# PIC_SENSOR-BOARD.net
KiCad netlist of a schematic drawn in EAGLE
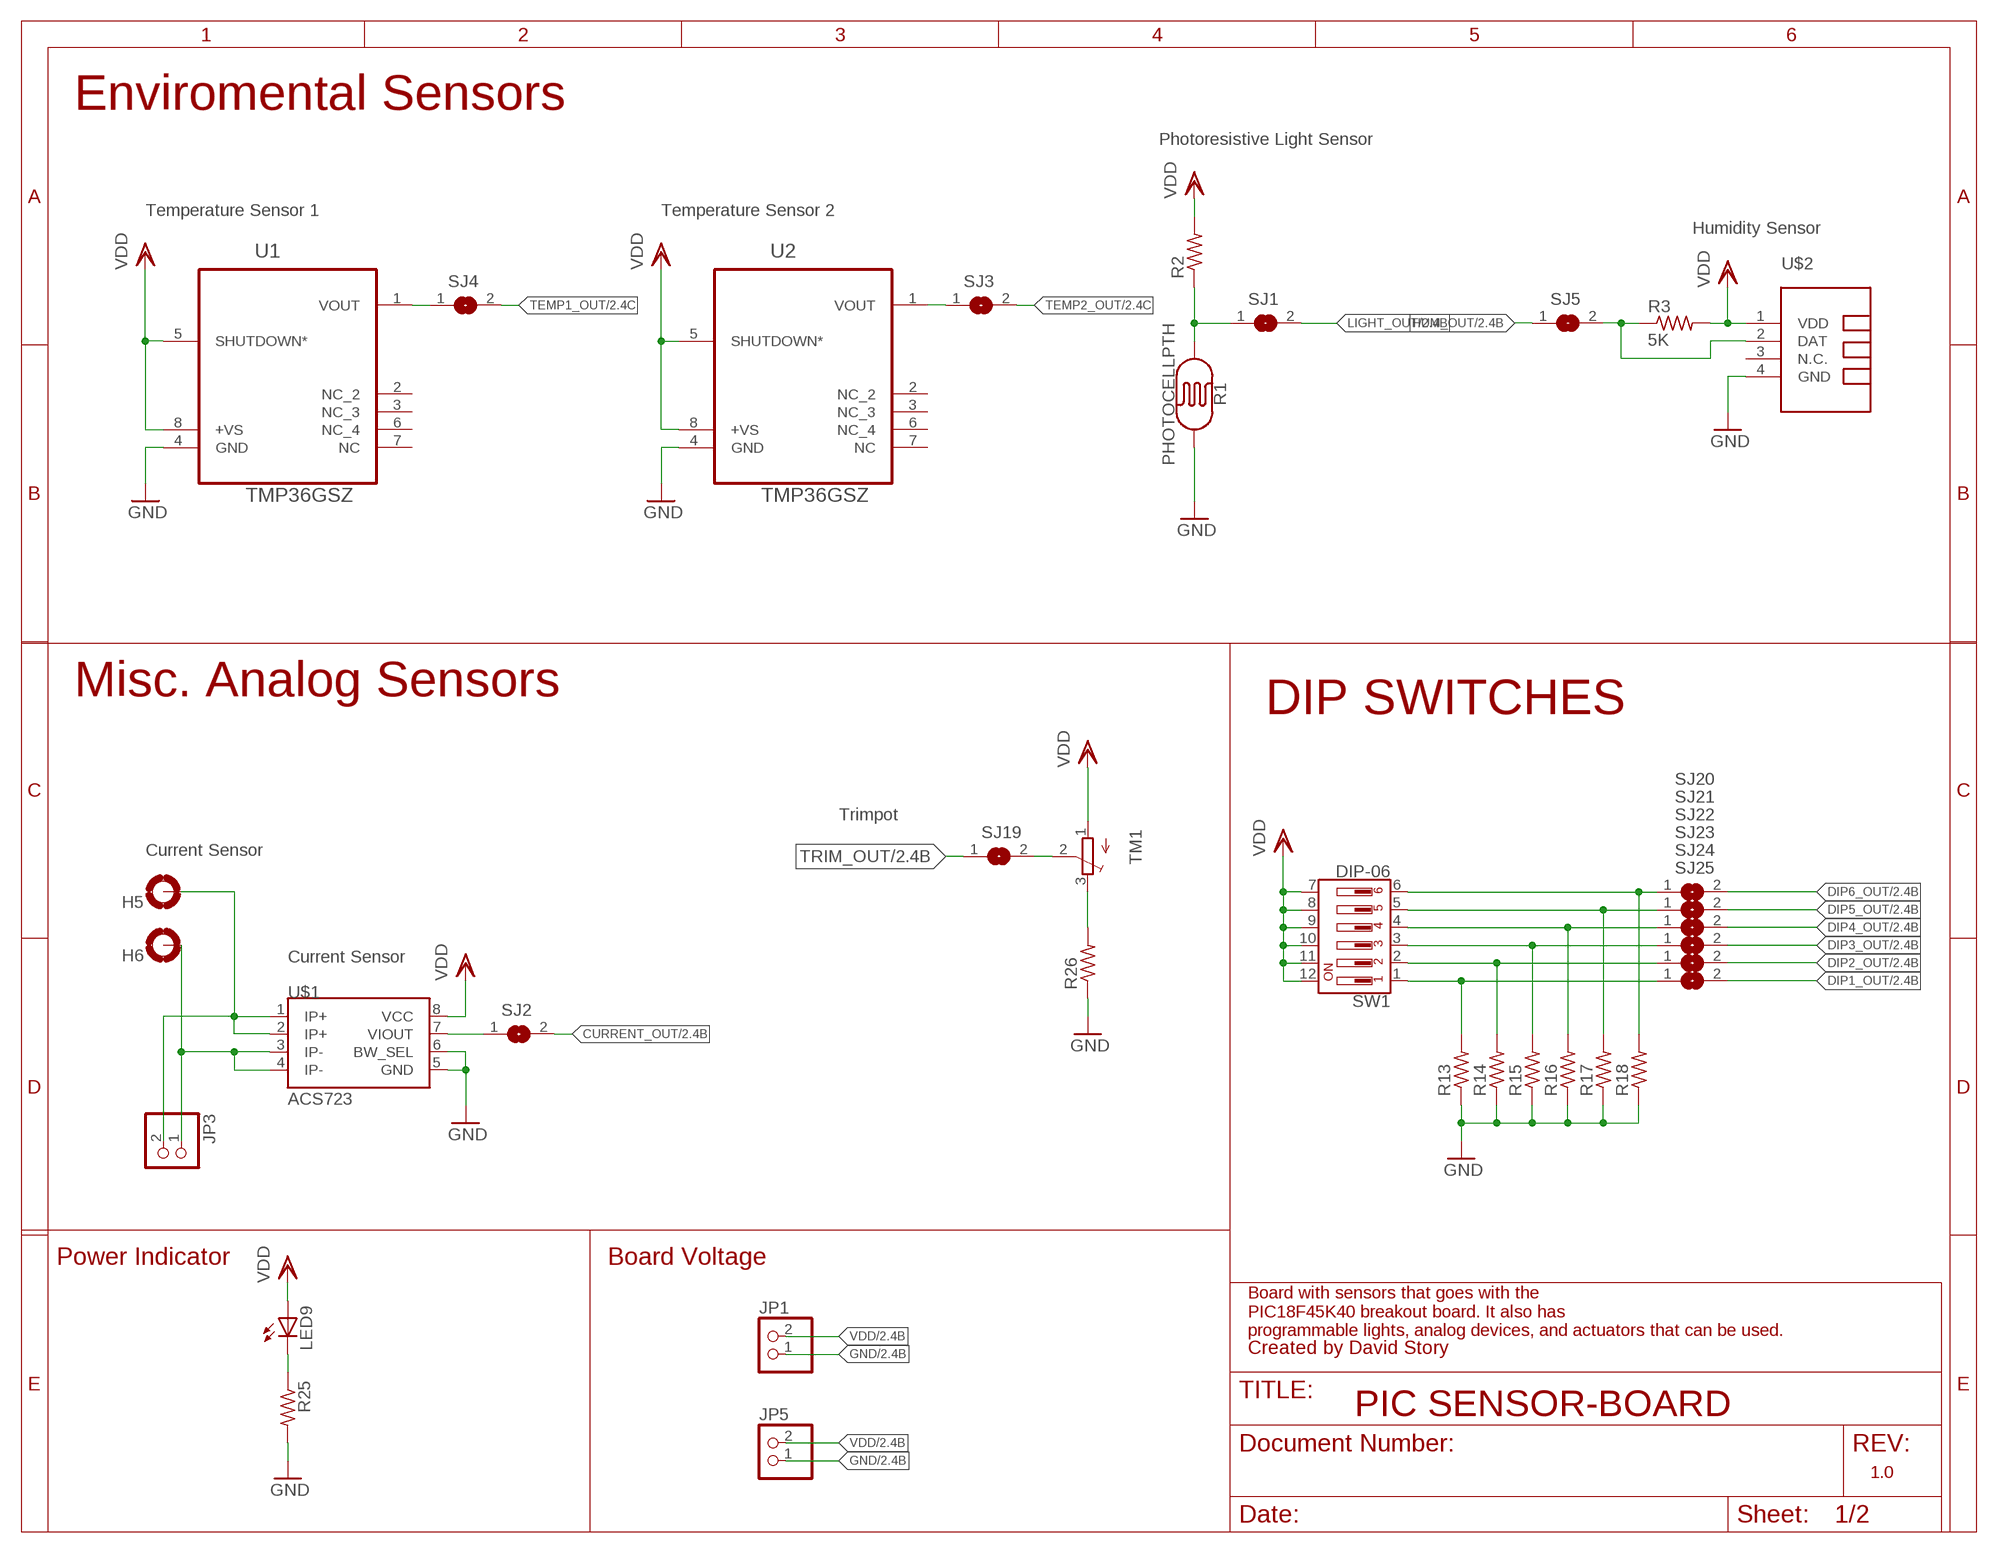
[diagram p0: schematic, sheet 1]
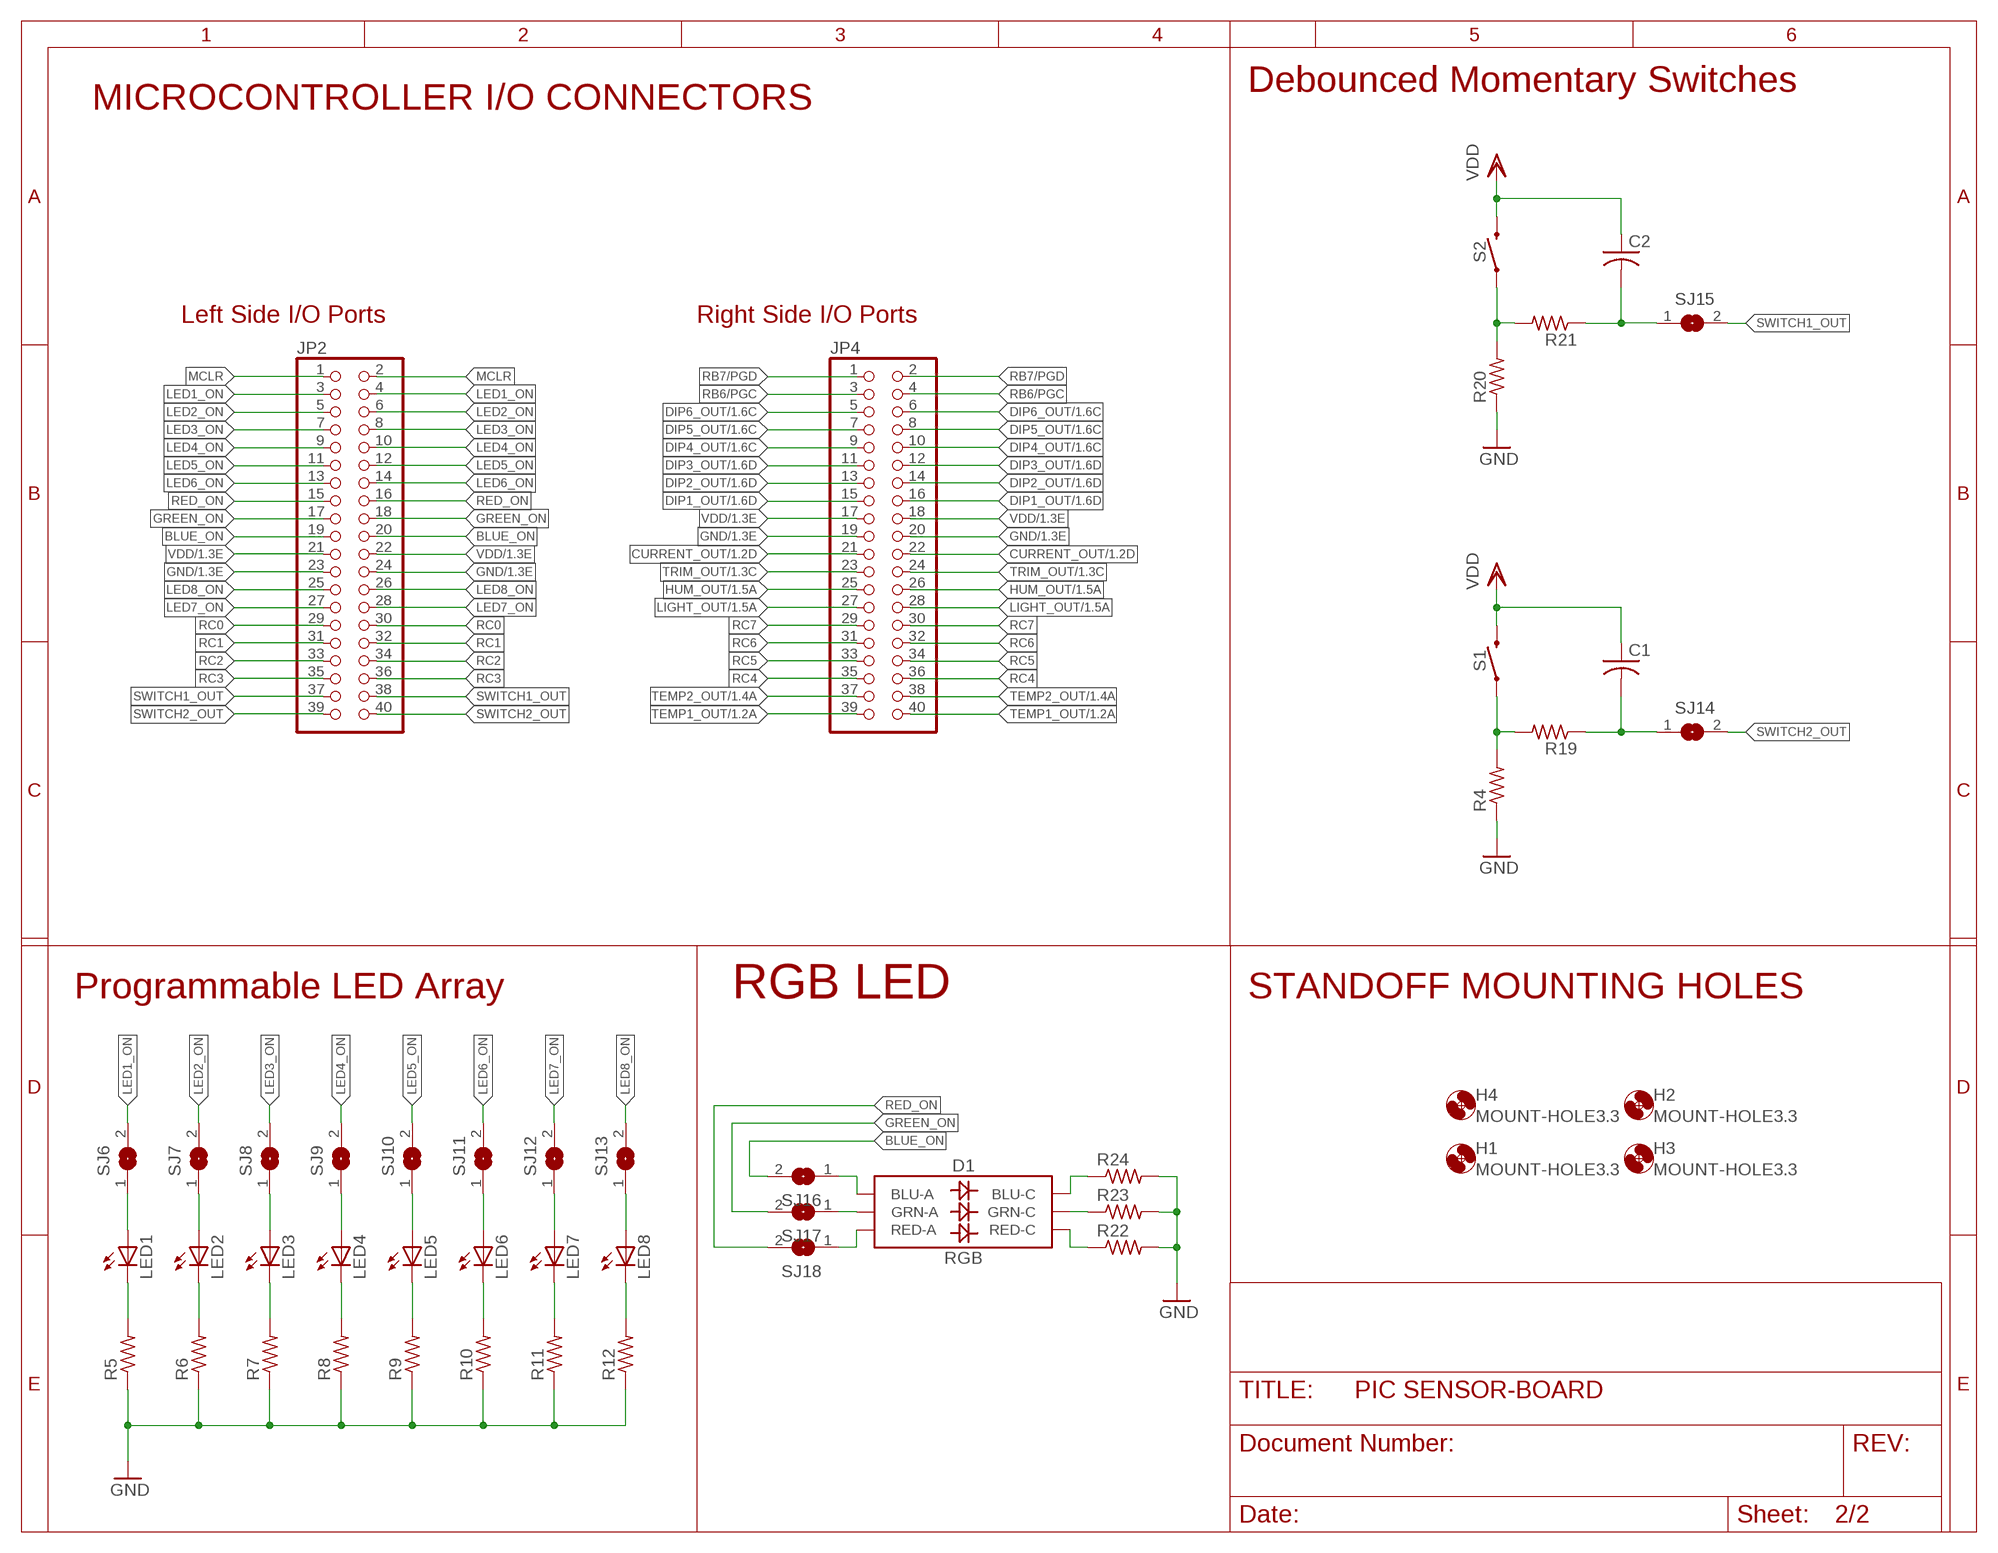
[diagram p1: schematic, sheet 2]

(export (version "E")
  (design (tool "Eeschema 10.0.6"))
  (components
    (comp (ref "H5")
      (value "MOUNT-PAD-ROUND3.3")
      (footprint "eagle-import:3,3-PAD")
      (libsource (lib "eagle-import") (part "MOUNT-PAD-ROUND3.3"))
    )
    (comp (ref "H6")
      (value "MOUNT-PAD-ROUND3.3")
      (footprint "eagle-import:3,3-PAD")
      (libsource (lib "eagle-import") (part "MOUNT-PAD-ROUND3.3"))
    )
    (comp (ref "JP1")
      (value "PINHD-1X2")
      (footprint "eagle-import:1X02")
      (libsource (lib "eagle-import") (part "PINHD-1X2"))
    )
    (comp (ref "JP3")
      (value "PINHD-1X2")
      (footprint "eagle-import:1X02")
      (libsource (lib "eagle-import") (part "PINHD-1X2"))
    )
    (comp (ref "JP5")
      (value "PINHD-1X2")
      (footprint "eagle-import:1X02")
      (libsource (lib "eagle-import") (part "PINHD-1X2"))
    )
    (comp (ref "LED9")
      (value "LEDCHIPLED_0603")
      (footprint "eagle-import:CHIPLED_0603")
      (libsource (lib "eagle-import") (part "LEDCHIPLED_0603"))
    )
    (comp (ref "R1")
      (value "PHOTOCELLPTH")
      (footprint "eagle-import:PHOTOCELL")
      (libsource (lib "eagle-import") (part "PHOTOCELLPTH"))
    )
    (comp (ref "R2")
      (value "R-US_M0805")
      (footprint "eagle-import:M0805")
      (libsource (lib "eagle-import") (part "R-US_M0805"))
    )
    (comp (ref "R3")
      (value "5K")
      (footprint "eagle-import:M0805")
      (libsource (lib "eagle-import") (part "R-US_M0805"))
    )
    (comp (ref "R13")
      (value "R-US_R0805")
      (footprint "eagle-import:R0805")
      (libsource (lib "eagle-import") (part "R-US_R0805"))
    )
    (comp (ref "R14")
      (value "R-US_R0805")
      (footprint "eagle-import:R0805")
      (libsource (lib "eagle-import") (part "R-US_R0805"))
    )
    (comp (ref "R15")
      (value "R-US_R0805")
      (footprint "eagle-import:R0805")
      (libsource (lib "eagle-import") (part "R-US_R0805"))
    )
    (comp (ref "R16")
      (value "R-US_R0805")
      (footprint "eagle-import:R0805")
      (libsource (lib "eagle-import") (part "R-US_R0805"))
    )
    (comp (ref "R17")
      (value "R-US_R0805")
      (footprint "eagle-import:R0805")
      (libsource (lib "eagle-import") (part "R-US_R0805"))
    )
    (comp (ref "R18")
      (value "R-US_R0805")
      (footprint "eagle-import:R0805")
      (libsource (lib "eagle-import") (part "R-US_R0805"))
    )
    (comp (ref "R25")
      (value "R-US_M0805")
      (footprint "eagle-import:M0805")
      (libsource (lib "eagle-import") (part "R-US_M0805"))
    )
    (comp (ref "R26")
      (value "R-US_M0805")
      (footprint "eagle-import:M0805")
      (libsource (lib "eagle-import") (part "R-US_M0805"))
    )
    (comp (ref "SJ1") (value "SJ") (footprint "eagle-import:SJ") (libsource (lib "eagle-import") (part "SJ")))
    (comp (ref "SJ2") (value "SJ") (footprint "eagle-import:SJ") (libsource (lib "eagle-import") (part "SJ")))
    (comp (ref "SJ3") (value "SJ") (footprint "eagle-import:SJ") (libsource (lib "eagle-import") (part "SJ")))
    (comp (ref "SJ4") (value "SJ") (footprint "eagle-import:SJ") (libsource (lib "eagle-import") (part "SJ")))
    (comp (ref "SJ5") (value "SJ") (footprint "eagle-import:SJ") (libsource (lib "eagle-import") (part "SJ")))
    (comp (ref "SJ19")
      (value "SJ")
      (footprint "eagle-import:SJ")
      (libsource (lib "eagle-import") (part "SJ"))
    )
    (comp (ref "SJ20")
      (value "SJ")
      (footprint "eagle-import:SJ")
      (libsource (lib "eagle-import") (part "SJ"))
    )
    (comp (ref "SJ21")
      (value "SJ")
      (footprint "eagle-import:SJ")
      (libsource (lib "eagle-import") (part "SJ"))
    )
    (comp (ref "SJ22")
      (value "SJ")
      (footprint "eagle-import:SJ")
      (libsource (lib "eagle-import") (part "SJ"))
    )
    (comp (ref "SJ23")
      (value "SJ")
      (footprint "eagle-import:SJ")
      (libsource (lib "eagle-import") (part "SJ"))
    )
    (comp (ref "SJ24")
      (value "SJ")
      (footprint "eagle-import:SJ")
      (libsource (lib "eagle-import") (part "SJ"))
    )
    (comp (ref "SJ25")
      (value "SJ")
      (footprint "eagle-import:SJ")
      (libsource (lib "eagle-import") (part "SJ"))
    )
    (comp (ref "SW1")
      (value "DIP-06")
      (footprint "eagle-import:DIPSWITCH-06-SMD")
      (libsource (lib "eagle-import") (part "DIP-06"))
    )
    (comp (ref "TM1")
      (value "TRIMPOT3386")
      (footprint "eagle-import:TRIM-3386")
      (libsource (lib "eagle-import") (part "TRIMPOT3386"))
    )
    (comp (ref "U$1")
      (value "ACS723")
      (footprint "eagle-import:SO08")
      (fields (field (name "PART_#") "ACS723ACS723LLCTR-05AB-T2"))
      (libsource (lib "eagle-import") (part "ACS723"))
    )
    (comp (ref "U$2")
      (value "TEMP-HUM-SENSOR-DHT11")
      (footprint "eagle-import:TEMP-HUM-SENSOR-DHT11")
      (libsource (lib "eagle-import") (part "TEMP-HUM-SENSOR-DHT11"))
    )
    (comp (ref "U1")
      (value "TMP36GSZ")
      (footprint "eagle-import:SOIC127P600X175-8N")
      (libsource (lib "eagle-import") (part "TMP36GSZ"))
    )
    (comp (ref "U2")
      (value "TMP36GSZ")
      (footprint "eagle-import:SOIC127P600X175-8N")
      (libsource (lib "eagle-import") (part "TMP36GSZ"))
    )
    (comp (ref "C1")
      (value "C-USC0805")
      (footprint "eagle-import:C0805")
      (libsource (lib "eagle-import") (part "C-USC0805"))
    )
    (comp (ref "C2")
      (value "C-USC0805")
      (footprint "eagle-import:C0805")
      (libsource (lib "eagle-import") (part "C-USC0805"))
    )
    (comp (ref "D1")
      (value "RGB")
      (footprint "eagle-import:PLCC-6-LED")
      (libsource (lib "eagle-import") (part "LED-RGBPLCC-6"))
    )
    (comp (ref "H1")
      (value "MOUNT-HOLE3.3")
      (footprint "eagle-import:3,3")
      (libsource (lib "eagle-import") (part "MOUNT-HOLE3.3"))
    )
    (comp (ref "H2")
      (value "MOUNT-HOLE3.3")
      (footprint "eagle-import:3,3")
      (libsource (lib "eagle-import") (part "MOUNT-HOLE3.3"))
    )
    (comp (ref "H3")
      (value "MOUNT-HOLE3.3")
      (footprint "eagle-import:3,3")
      (libsource (lib "eagle-import") (part "MOUNT-HOLE3.3"))
    )
    (comp (ref "H4")
      (value "MOUNT-HOLE3.3")
      (footprint "eagle-import:3,3")
      (libsource (lib "eagle-import") (part "MOUNT-HOLE3.3"))
    )
    (comp (ref "JP2")
      (value "PINHD-2X20")
      (footprint "eagle-import:2X20")
      (libsource (lib "eagle-import") (part "PINHD-2X20"))
    )
    (comp (ref "JP4")
      (value "PINHD-2X20")
      (footprint "eagle-import:2X20")
      (libsource (lib "eagle-import") (part "PINHD-2X20"))
    )
    (comp (ref "LED1")
      (value "LEDSML0603")
      (footprint "eagle-import:SML0603")
      (libsource (lib "eagle-import") (part "LEDSML0603"))
    )
    (comp (ref "LED2")
      (value "LEDSML0603")
      (footprint "eagle-import:SML0603")
      (libsource (lib "eagle-import") (part "LEDSML0603"))
    )
    (comp (ref "LED3")
      (value "LEDSML0603")
      (footprint "eagle-import:SML0603")
      (libsource (lib "eagle-import") (part "LEDSML0603"))
    )
    (comp (ref "LED4")
      (value "LEDSML0603")
      (footprint "eagle-import:SML0603")
      (libsource (lib "eagle-import") (part "LEDSML0603"))
    )
    (comp (ref "LED5")
      (value "LEDSML0603")
      (footprint "eagle-import:SML0603")
      (libsource (lib "eagle-import") (part "LEDSML0603"))
    )
    (comp (ref "LED6")
      (value "LEDSML0603")
      (footprint "eagle-import:SML0603")
      (libsource (lib "eagle-import") (part "LEDSML0603"))
    )
    (comp (ref "LED7")
      (value "LEDSML0603")
      (footprint "eagle-import:SML0603")
      (libsource (lib "eagle-import") (part "LEDSML0603"))
    )
    (comp (ref "LED8")
      (value "LEDSML0603")
      (footprint "eagle-import:SML0603")
      (libsource (lib "eagle-import") (part "LEDSML0603"))
    )
    (comp (ref "R4")
      (value "R-US_M0805")
      (footprint "eagle-import:M0805")
      (libsource (lib "eagle-import") (part "R-US_M0805"))
    )
    (comp (ref "R5")
      (value "R-US_M0805")
      (footprint "eagle-import:M0805")
      (libsource (lib "eagle-import") (part "R-US_M0805"))
    )
    (comp (ref "R6")
      (value "R-US_M0805")
      (footprint "eagle-import:M0805")
      (libsource (lib "eagle-import") (part "R-US_M0805"))
    )
    (comp (ref "R7")
      (value "R-US_M0805")
      (footprint "eagle-import:M0805")
      (libsource (lib "eagle-import") (part "R-US_M0805"))
    )
    (comp (ref "R8")
      (value "R-US_M0805")
      (footprint "eagle-import:M0805")
      (libsource (lib "eagle-import") (part "R-US_M0805"))
    )
    (comp (ref "R9")
      (value "R-US_M0805")
      (footprint "eagle-import:M0805")
      (libsource (lib "eagle-import") (part "R-US_M0805"))
    )
    (comp (ref "R10")
      (value "R-US_M0805")
      (footprint "eagle-import:M0805")
      (libsource (lib "eagle-import") (part "R-US_M0805"))
    )
    (comp (ref "R11")
      (value "R-US_M0805")
      (footprint "eagle-import:M0805")
      (libsource (lib "eagle-import") (part "R-US_M0805"))
    )
    (comp (ref "R12")
      (value "R-US_M0805")
      (footprint "eagle-import:M0805")
      (libsource (lib "eagle-import") (part "R-US_M0805"))
    )
    (comp (ref "R19")
      (value "R-US_M0805")
      (footprint "eagle-import:M0805")
      (libsource (lib "eagle-import") (part "R-US_M0805"))
    )
    (comp (ref "R20")
      (value "R-US_M0805")
      (footprint "eagle-import:M0805")
      (libsource (lib "eagle-import") (part "R-US_M0805"))
    )
    (comp (ref "R21")
      (value "R-US_M0805")
      (footprint "eagle-import:M0805")
      (libsource (lib "eagle-import") (part "R-US_M0805"))
    )
    (comp (ref "R22")
      (value "R-US_R0805")
      (footprint "eagle-import:R0805")
      (libsource (lib "eagle-import") (part "R-US_R0805"))
    )
    (comp (ref "R23")
      (value "R-US_R0805")
      (footprint "eagle-import:R0805")
      (libsource (lib "eagle-import") (part "R-US_R0805"))
    )
    (comp (ref "R24")
      (value "R-US_R0805")
      (footprint "eagle-import:R0805")
      (libsource (lib "eagle-import") (part "R-US_R0805"))
    )
    (comp (ref "S1")
      (value "MOMENTARY-SWITCH-SPST-PTH-6.0MM")
      (footprint "eagle-import:TACTILE_SWITCH_PTH_6.0MM")
      (libsource (lib "eagle-import") (part "MOMENTARY-SWITCH-SPST-PTH-6.0MM"))
    )
    (comp (ref "S2")
      (value "MOMENTARY-SWITCH-SPST-PTH-6.0MM")
      (footprint "eagle-import:TACTILE_SWITCH_PTH_6.0MM")
      (libsource (lib "eagle-import") (part "MOMENTARY-SWITCH-SPST-PTH-6.0MM"))
    )
    (comp (ref "SJ6") (value "SJ") (footprint "eagle-import:SJ") (libsource (lib "eagle-import") (part "SJ")))
    (comp (ref "SJ7") (value "SJ") (footprint "eagle-import:SJ") (libsource (lib "eagle-import") (part "SJ")))
    (comp (ref "SJ8") (value "SJ") (footprint "eagle-import:SJ") (libsource (lib "eagle-import") (part "SJ")))
    (comp (ref "SJ9") (value "SJ") (footprint "eagle-import:SJ") (libsource (lib "eagle-import") (part "SJ")))
    (comp (ref "SJ10")
      (value "SJ")
      (footprint "eagle-import:SJ")
      (libsource (lib "eagle-import") (part "SJ"))
    )
    (comp (ref "SJ11")
      (value "SJ")
      (footprint "eagle-import:SJ")
      (libsource (lib "eagle-import") (part "SJ"))
    )
    (comp (ref "SJ12")
      (value "SJ")
      (footprint "eagle-import:SJ")
      (libsource (lib "eagle-import") (part "SJ"))
    )
    (comp (ref "SJ13")
      (value "SJ")
      (footprint "eagle-import:SJ")
      (libsource (lib "eagle-import") (part "SJ"))
    )
    (comp (ref "SJ14")
      (value "SJ")
      (footprint "eagle-import:SJ")
      (libsource (lib "eagle-import") (part "SJ"))
    )
    (comp (ref "SJ15")
      (value "SJ")
      (footprint "eagle-import:SJ")
      (libsource (lib "eagle-import") (part "SJ"))
    )
    (comp (ref "SJ16")
      (value "SJ")
      (footprint "eagle-import:SJ")
      (libsource (lib "eagle-import") (part "SJ"))
    )
    (comp (ref "SJ17")
      (value "SJ")
      (footprint "eagle-import:SJ")
      (libsource (lib "eagle-import") (part "SJ"))
    )
    (comp (ref "SJ18")
      (value "SJ")
      (footprint "eagle-import:SJ")
      (libsource (lib "eagle-import") (part "SJ"))
    )
  )
  (nets
    (net (code "1") (name "BLUE_ON") (class "Default")
      (node (ref "JP2") (pin "19") (pinfunction "19_19") (pintype "passive"))
      (node (ref "JP2") (pin "20") (pinfunction "20_20") (pintype "passive"))
      (node (ref "SJ16") (pin "2") (pinfunction "2_2") (pintype "passive"))
    )
    (net (code "2") (name "CURRENT_OUT") (class "Default")
      (node (ref "JP4") (pin "21") (pinfunction "21_21") (pintype "passive"))
      (node (ref "JP4") (pin "22") (pinfunction "22_22") (pintype "passive"))
      (node (ref "SJ2") (pin "2") (pinfunction "2_2") (pintype "passive"))
    )
    (net (code "3") (name "DIP1_OUT") (class "Default")
      (node (ref "JP4") (pin "15") (pinfunction "15_15") (pintype "passive"))
      (node (ref "JP4") (pin "16") (pinfunction "16_16") (pintype "passive"))
      (node (ref "SJ25") (pin "2") (pinfunction "2_2") (pintype "passive"))
    )
    (net (code "4") (name "DIP2_OUT") (class "Default")
      (node (ref "JP4") (pin "13") (pinfunction "13_13") (pintype "passive"))
      (node (ref "JP4") (pin "14") (pinfunction "14_14") (pintype "passive"))
      (node (ref "SJ24") (pin "2") (pinfunction "2_2") (pintype "passive"))
    )
    (net (code "5") (name "DIP3_OUT") (class "Default")
      (node (ref "JP4") (pin "11") (pinfunction "11_11") (pintype "passive"))
      (node (ref "JP4") (pin "12") (pinfunction "12_12") (pintype "passive"))
      (node (ref "SJ23") (pin "2") (pinfunction "2_2") (pintype "passive"))
    )
    (net (code "6") (name "DIP4_OUT") (class "Default")
      (node (ref "JP4") (pin "10") (pinfunction "10_10") (pintype "passive"))
      (node (ref "JP4") (pin "9") (pinfunction "9_9") (pintype "passive"))
      (node (ref "SJ22") (pin "2") (pinfunction "2_2") (pintype "passive"))
    )
    (net (code "7") (name "DIP5_OUT") (class "Default")
      (node (ref "JP4") (pin "7") (pinfunction "7_7") (pintype "passive"))
      (node (ref "JP4") (pin "8") (pinfunction "8_8") (pintype "passive"))
      (node (ref "SJ21") (pin "2") (pinfunction "2_2") (pintype "passive"))
    )
    (net (code "8") (name "DIP6_OUT") (class "Default")
      (node (ref "JP4") (pin "5") (pinfunction "5_5") (pintype "passive"))
      (node (ref "JP4") (pin "6") (pinfunction "6_6") (pintype "passive"))
      (node (ref "SJ20") (pin "2") (pinfunction "2_2") (pintype "passive"))
    )
    (net (code "9") (name "GND") (class "Default")
      (node (ref "JP1") (pin "1") (pinfunction "1_1") (pintype "passive"))
      (node (ref "JP2") (pin "23") (pinfunction "23_23") (pintype "passive"))
      (node (ref "JP2") (pin "24") (pinfunction "24_24") (pintype "passive"))
      (node (ref "JP4") (pin "19") (pinfunction "19_19") (pintype "passive"))
      (node (ref "JP4") (pin "20") (pinfunction "20_20") (pintype "passive"))
      (node (ref "JP5") (pin "1") (pinfunction "1_1") (pintype "passive"))
      (node (ref "R1") (pin "2") (pinfunction "P$2_2") (pintype "bidirectional"))
      (node (ref "R10") (pin "1") (pinfunction "1_1") (pintype "passive"))
      (node (ref "R11") (pin "1") (pinfunction "1_1") (pintype "passive"))
      (node (ref "R12") (pin "1") (pinfunction "1_1") (pintype "passive"))
      (node (ref "R13") (pin "1") (pinfunction "1_1") (pintype "passive"))
      (node (ref "R14") (pin "1") (pinfunction "1_1") (pintype "passive"))
      (node (ref "R15") (pin "1") (pinfunction "1_1") (pintype "passive"))
      (node (ref "R16") (pin "1") (pinfunction "1_1") (pintype "passive"))
      (node (ref "R17") (pin "1") (pinfunction "1_1") (pintype "passive"))
      (node (ref "R18") (pin "1") (pinfunction "1_1") (pintype "passive"))
      (node (ref "R20") (pin "1") (pinfunction "1_1") (pintype "passive"))
      (node (ref "R22") (pin "2") (pinfunction "2_2") (pintype "passive"))
      (node (ref "R23") (pin "2") (pinfunction "2_2") (pintype "passive"))
      (node (ref "R24") (pin "2") (pinfunction "2_2") (pintype "passive"))
      (node (ref "R25") (pin "2") (pinfunction "2_2") (pintype "passive"))
      (node (ref "R26") (pin "1") (pinfunction "1_1") (pintype "passive"))
      (node (ref "R4") (pin "1") (pinfunction "1_1") (pintype "passive"))
      (node (ref "R5") (pin "1") (pinfunction "1_1") (pintype "passive"))
      (node (ref "R6") (pin "1") (pinfunction "1_1") (pintype "passive"))
      (node (ref "R7") (pin "1") (pinfunction "1_1") (pintype "passive"))
      (node (ref "R8") (pin "1") (pinfunction "1_1") (pintype "passive"))
      (node (ref "R9") (pin "1") (pinfunction "1_1") (pintype "passive"))
      (node (ref "U$1") (pin "5") (pinfunction "GND_5") (pintype "bidirectional"))
      (node (ref "U$1") (pin "6") (pinfunction "BW_SEL_6") (pintype "bidirectional"))
      (node (ref "U$2") (pin "4") (pinfunction "GND_4") (pintype "power_in"))
      (node (ref "U1") (pin "4") (pinfunction "GND_4") (pintype "passive"))
      (node (ref "U2") (pin "4") (pinfunction "GND_4") (pintype "passive"))
    )
    (net (code "10") (name "GREEN_ON") (class "Default")
      (node (ref "JP2") (pin "17") (pinfunction "17_17") (pintype "passive"))
      (node (ref "JP2") (pin "18") (pinfunction "18_18") (pintype "passive"))
      (node (ref "SJ17") (pin "2") (pinfunction "2_2") (pintype "passive"))
    )
    (net (code "11") (name "HUM_OUT") (class "Default")
      (node (ref "JP4") (pin "25") (pinfunction "25_25") (pintype "passive"))
      (node (ref "JP4") (pin "26") (pinfunction "26_26") (pintype "passive"))
      (node (ref "SJ5") (pin "1") (pinfunction "1_1") (pintype "passive"))
    )
    (net (code "12") (name "LED1_ON") (class "Default")
      (node (ref "JP2") (pin "3") (pinfunction "3_3") (pintype "passive"))
      (node (ref "JP2") (pin "4") (pinfunction "4_4") (pintype "passive"))
      (node (ref "SJ6") (pin "2") (pinfunction "2_2") (pintype "passive"))
    )
    (net (code "13") (name "LED2_ON") (class "Default")
      (node (ref "JP2") (pin "5") (pinfunction "5_5") (pintype "passive"))
      (node (ref "JP2") (pin "6") (pinfunction "6_6") (pintype "passive"))
      (node (ref "SJ7") (pin "2") (pinfunction "2_2") (pintype "passive"))
    )
    (net (code "14") (name "LED3_ON") (class "Default")
      (node (ref "JP2") (pin "7") (pinfunction "7_7") (pintype "passive"))
      (node (ref "JP2") (pin "8") (pinfunction "8_8") (pintype "passive"))
      (node (ref "SJ8") (pin "2") (pinfunction "2_2") (pintype "passive"))
    )
    (net (code "15") (name "LED4_ON") (class "Default")
      (node (ref "JP2") (pin "10") (pinfunction "10_10") (pintype "passive"))
      (node (ref "JP2") (pin "9") (pinfunction "9_9") (pintype "passive"))
      (node (ref "SJ9") (pin "2") (pinfunction "2_2") (pintype "passive"))
    )
    (net (code "16") (name "LED5_ON") (class "Default")
      (node (ref "JP2") (pin "11") (pinfunction "11_11") (pintype "passive"))
      (node (ref "JP2") (pin "12") (pinfunction "12_12") (pintype "passive"))
      (node (ref "SJ10") (pin "2") (pinfunction "2_2") (pintype "passive"))
    )
    (net (code "17") (name "LED6_ON") (class "Default")
      (node (ref "JP2") (pin "13") (pinfunction "13_13") (pintype "passive"))
      (node (ref "JP2") (pin "14") (pinfunction "14_14") (pintype "passive"))
      (node (ref "SJ11") (pin "2") (pinfunction "2_2") (pintype "passive"))
    )
    (net (code "18") (name "LED7_ON") (class "Default")
      (node (ref "JP2") (pin "27") (pinfunction "27_27") (pintype "passive"))
      (node (ref "JP2") (pin "28") (pinfunction "28_28") (pintype "passive"))
      (node (ref "SJ12") (pin "2") (pinfunction "2_2") (pintype "passive"))
    )
    (net (code "19") (name "LED8_ON") (class "Default")
      (node (ref "JP2") (pin "25") (pinfunction "25_25") (pintype "passive"))
      (node (ref "JP2") (pin "26") (pinfunction "26_26") (pintype "passive"))
      (node (ref "SJ13") (pin "2") (pinfunction "2_2") (pintype "passive"))
    )
    (net (code "20") (name "LIGHT_OUT") (class "Default")
      (node (ref "JP4") (pin "27") (pinfunction "27_27") (pintype "passive"))
      (node (ref "JP4") (pin "28") (pinfunction "28_28") (pintype "passive"))
      (node (ref "SJ1") (pin "2") (pinfunction "2_2") (pintype "passive"))
    )
    (net (code "21") (name "MCLR") (class "Default")
      (node (ref "JP2") (pin "1") (pinfunction "1_1") (pintype "passive"))
      (node (ref "JP2") (pin "2") (pinfunction "2_2") (pintype "passive"))
    )
    (net (code "22") (name "Net-(C1-Pad2)") (class "Default")
      (node (ref "C1") (pin "2") (pinfunction "2_2") (pintype "passive"))
      (node (ref "R19") (pin "1") (pinfunction "1_1") (pintype "passive"))
      (node (ref "SJ14") (pin "1") (pinfunction "1_1") (pintype "passive"))
    )
    (net (code "23") (name "Net-(C2-Pad2)") (class "Default")
      (node (ref "C2") (pin "2") (pinfunction "2_2") (pintype "passive"))
      (node (ref "R21") (pin "1") (pinfunction "1_1") (pintype "passive"))
      (node (ref "SJ15") (pin "1") (pinfunction "1_1") (pintype "passive"))
    )
    (net (code "24") (name "Net-(D1-BLU-A)") (class "Default")
      (node (ref "D1") (pin "AB") (pinfunction "BLU-A_AB") (pintype "bidirectional"))
      (node (ref "SJ16") (pin "1") (pinfunction "1_1") (pintype "passive"))
    )
    (net (code "25") (name "Net-(D1-BLU-C)") (class "Default")
      (node (ref "D1") (pin "CB") (pinfunction "BLU-C_CB") (pintype "bidirectional"))
      (node (ref "R24") (pin "1") (pinfunction "1_1") (pintype "passive"))
    )
    (net (code "26") (name "Net-(D1-GRN-A)") (class "Default")
      (node (ref "D1") (pin "AG") (pinfunction "GRN-A_AG") (pintype "bidirectional"))
      (node (ref "SJ17") (pin "1") (pinfunction "1_1") (pintype "passive"))
    )
    (net (code "27") (name "Net-(D1-GRN-C)") (class "Default")
      (node (ref "D1") (pin "CG") (pinfunction "GRN-C_CG") (pintype "bidirectional"))
      (node (ref "R23") (pin "1") (pinfunction "1_1") (pintype "passive"))
    )
    (net (code "28") (name "Net-(D1-RED-A)") (class "Default")
      (node (ref "D1") (pin "AR") (pinfunction "RED-A_AR") (pintype "bidirectional"))
      (node (ref "SJ18") (pin "1") (pinfunction "1_1") (pintype "passive"))
    )
    (net (code "29") (name "Net-(D1-RED-C)") (class "Default")
      (node (ref "D1") (pin "CR") (pinfunction "RED-C_CR") (pintype "bidirectional"))
      (node (ref "R22") (pin "1") (pinfunction "1_1") (pintype "passive"))
    )
    (net (code "30") (name "Net-(H5-MOUNT)") (class "Default")
      (node (ref "H5") (pin "B3,3") (pinfunction "MOUNT_B3,3") (pintype "passive"))
      (node (ref "JP3") (pin "2") (pinfunction "2_2") (pintype "passive"))
      (node (ref "U$1") (pin "1") (pinfunction "IP+_1") (pintype "input"))
      (node (ref "U$1") (pin "2") (pinfunction "IP+_2") (pintype "input"))
    )
    (net (code "31") (name "Net-(H6-MOUNT)") (class "Default")
      (node (ref "H6") (pin "B3,3") (pinfunction "MOUNT_B3,3") (pintype "passive"))
      (node (ref "JP3") (pin "1") (pinfunction "1_1") (pintype "passive"))
      (node (ref "U$1") (pin "3") (pinfunction "IP-_3") (pintype "bidirectional"))
      (node (ref "U$1") (pin "4") (pinfunction "IP-_4") (pintype "bidirectional"))
    )
    (net (code "32") (name "Net-(LED1-PadA)") (class "Default")
      (node (ref "LED1") (pin "A") (pinfunction "A_A") (pintype "passive"))
      (node (ref "SJ6") (pin "1") (pinfunction "1_1") (pintype "passive"))
    )
    (net (code "33") (name "Net-(LED1-PadC)") (class "Default")
      (node (ref "LED1") (pin "C") (pinfunction "C_C") (pintype "passive"))
      (node (ref "R5") (pin "2") (pinfunction "2_2") (pintype "passive"))
    )
    (net (code "34") (name "Net-(LED2-PadA)") (class "Default")
      (node (ref "LED2") (pin "A") (pinfunction "A_A") (pintype "passive"))
      (node (ref "SJ7") (pin "1") (pinfunction "1_1") (pintype "passive"))
    )
    (net (code "35") (name "Net-(LED2-PadC)") (class "Default")
      (node (ref "LED2") (pin "C") (pinfunction "C_C") (pintype "passive"))
      (node (ref "R6") (pin "2") (pinfunction "2_2") (pintype "passive"))
    )
    (net (code "36") (name "Net-(LED3-PadA)") (class "Default")
      (node (ref "LED3") (pin "A") (pinfunction "A_A") (pintype "passive"))
      (node (ref "SJ8") (pin "1") (pinfunction "1_1") (pintype "passive"))
    )
    (net (code "37") (name "Net-(LED3-PadC)") (class "Default")
      (node (ref "LED3") (pin "C") (pinfunction "C_C") (pintype "passive"))
      (node (ref "R7") (pin "2") (pinfunction "2_2") (pintype "passive"))
    )
    (net (code "38") (name "Net-(LED4-PadA)") (class "Default")
      (node (ref "LED4") (pin "A") (pinfunction "A_A") (pintype "passive"))
      (node (ref "SJ9") (pin "1") (pinfunction "1_1") (pintype "passive"))
    )
    (net (code "39") (name "Net-(LED4-PadC)") (class "Default")
      (node (ref "LED4") (pin "C") (pinfunction "C_C") (pintype "passive"))
      (node (ref "R8") (pin "2") (pinfunction "2_2") (pintype "passive"))
    )
    (net (code "40") (name "Net-(LED5-PadA)") (class "Default")
      (node (ref "LED5") (pin "A") (pinfunction "A_A") (pintype "passive"))
      (node (ref "SJ10") (pin "1") (pinfunction "1_1") (pintype "passive"))
    )
    (net (code "41") (name "Net-(LED5-PadC)") (class "Default")
      (node (ref "LED5") (pin "C") (pinfunction "C_C") (pintype "passive"))
      (node (ref "R9") (pin "2") (pinfunction "2_2") (pintype "passive"))
    )
    (net (code "42") (name "Net-(LED6-PadA)") (class "Default")
      (node (ref "LED6") (pin "A") (pinfunction "A_A") (pintype "passive"))
      (node (ref "SJ11") (pin "1") (pinfunction "1_1") (pintype "passive"))
    )
    (net (code "43") (name "Net-(LED6-PadC)") (class "Default")
      (node (ref "LED6") (pin "C") (pinfunction "C_C") (pintype "passive"))
      (node (ref "R10") (pin "2") (pinfunction "2_2") (pintype "passive"))
    )
    (net (code "44") (name "Net-(LED7-PadA)") (class "Default")
      (node (ref "LED7") (pin "A") (pinfunction "A_A") (pintype "passive"))
      (node (ref "SJ12") (pin "1") (pinfunction "1_1") (pintype "passive"))
    )
    (net (code "45") (name "Net-(LED7-PadC)") (class "Default")
      (node (ref "LED7") (pin "C") (pinfunction "C_C") (pintype "passive"))
      (node (ref "R11") (pin "2") (pinfunction "2_2") (pintype "passive"))
    )
    (net (code "46") (name "Net-(LED8-PadA)") (class "Default")
      (node (ref "LED8") (pin "A") (pinfunction "A_A") (pintype "passive"))
      (node (ref "SJ13") (pin "1") (pinfunction "1_1") (pintype "passive"))
    )
    (net (code "47") (name "Net-(LED8-PadC)") (class "Default")
      (node (ref "LED8") (pin "C") (pinfunction "C_C") (pintype "passive"))
      (node (ref "R12") (pin "2") (pinfunction "2_2") (pintype "passive"))
    )
    (net (code "48") (name "Net-(LED9-PadC)") (class "Default")
      (node (ref "LED9") (pin "C") (pinfunction "C_C") (pintype "passive"))
      (node (ref "R25") (pin "1") (pinfunction "1_1") (pintype "passive"))
    )
    (net (code "49") (name "Net-(R1-P$1)") (class "Default")
      (node (ref "R1") (pin "1") (pinfunction "P$1_1") (pintype "bidirectional"))
      (node (ref "R2") (pin "1") (pinfunction "1_1") (pintype "passive"))
      (node (ref "SJ1") (pin "1") (pinfunction "1_1") (pintype "passive"))
    )
    (net (code "50") (name "Net-(R13-Pad2)") (class "Default")
      (node (ref "R13") (pin "2") (pinfunction "2_2") (pintype "passive"))
      (node (ref "SJ25") (pin "1") (pinfunction "1_1") (pintype "passive"))
      (node (ref "SW1") (pin "1") (pinfunction "1_1") (pintype "bidirectional"))
    )
    (net (code "51") (name "Net-(R14-Pad2)") (class "Default")
      (node (ref "R14") (pin "2") (pinfunction "2_2") (pintype "passive"))
      (node (ref "SJ24") (pin "1") (pinfunction "1_1") (pintype "passive"))
      (node (ref "SW1") (pin "2") (pinfunction "2_2") (pintype "bidirectional"))
    )
    (net (code "52") (name "Net-(R15-Pad2)") (class "Default")
      (node (ref "R15") (pin "2") (pinfunction "2_2") (pintype "passive"))
      (node (ref "SJ23") (pin "1") (pinfunction "1_1") (pintype "passive"))
      (node (ref "SW1") (pin "3") (pinfunction "3_3") (pintype "bidirectional"))
    )
    (net (code "53") (name "Net-(R16-Pad2)") (class "Default")
      (node (ref "R16") (pin "2") (pinfunction "2_2") (pintype "passive"))
      (node (ref "SJ22") (pin "1") (pinfunction "1_1") (pintype "passive"))
      (node (ref "SW1") (pin "4") (pinfunction "4_4") (pintype "bidirectional"))
    )
    (net (code "54") (name "Net-(R17-Pad2)") (class "Default")
      (node (ref "R17") (pin "2") (pinfunction "2_2") (pintype "passive"))
      (node (ref "SJ21") (pin "1") (pinfunction "1_1") (pintype "passive"))
      (node (ref "SW1") (pin "5") (pinfunction "5_5") (pintype "bidirectional"))
    )
    (net (code "55") (name "Net-(R18-Pad2)") (class "Default")
      (node (ref "R18") (pin "2") (pinfunction "2_2") (pintype "passive"))
      (node (ref "SJ20") (pin "1") (pinfunction "1_1") (pintype "passive"))
      (node (ref "SW1") (pin "6") (pinfunction "6_6") (pintype "bidirectional"))
    )
    (net (code "56") (name "Net-(R19-Pad2)") (class "Default")
      (node (ref "R19") (pin "2") (pinfunction "2_2") (pintype "passive"))
      (node (ref "R4") (pin "2") (pinfunction "2_2") (pintype "passive"))
      (node (ref "S1") (pin "1") (pinfunction "1_1") (pintype "passive"))
    )
    (net (code "57") (name "Net-(R20-Pad2)") (class "Default")
      (node (ref "R20") (pin "2") (pinfunction "2_2") (pintype "passive"))
      (node (ref "R21") (pin "2") (pinfunction "2_2") (pintype "passive"))
      (node (ref "S2") (pin "1") (pinfunction "1_1") (pintype "passive"))
    )
    (net (code "58") (name "Net-(TM1-E)") (class "Default")
      (node (ref "R26") (pin "2") (pinfunction "2_2") (pintype "passive"))
      (node (ref "TM1") (pin "3") (pinfunction "E_3") (pintype "passive"))
    )
    (net (code "59") (name "Net-(TM1-S)") (class "Default")
      (node (ref "SJ19") (pin "2") (pinfunction "2_2") (pintype "passive"))
      (node (ref "TM1") (pin "2") (pinfunction "S_2") (pintype "passive"))
    )
    (net (code "60") (name "Net-(U$1-VIOUT)") (class "Default")
      (node (ref "SJ2") (pin "1") (pinfunction "1_1") (pintype "passive"))
      (node (ref "U$1") (pin "7") (pinfunction "VIOUT_7") (pintype "bidirectional"))
    )
    (net (code "61") (name "Net-(U$2-DAT)") (class "Default")
      (node (ref "R3") (pin "1") (pinfunction "1_1") (pintype "passive"))
      (node (ref "SJ5") (pin "2") (pinfunction "2_2") (pintype "passive"))
      (node (ref "U$2") (pin "2") (pinfunction "DAT_2") (pintype "bidirectional"))
    )
    (net (code "62") (name "Net-(U1-VOUT)") (class "Default")
      (node (ref "SJ4") (pin "1") (pinfunction "1_1") (pintype "passive"))
      (node (ref "U1") (pin "1") (pinfunction "VOUT_1") (pintype "passive"))
    )
    (net (code "63") (name "Net-(U2-VOUT)") (class "Default")
      (node (ref "SJ3") (pin "1") (pinfunction "1_1") (pintype "passive"))
      (node (ref "U2") (pin "1") (pinfunction "VOUT_1") (pintype "passive"))
    )
    (net (code "64") (name "RB6{slash}PGC") (class "Default")
      (node (ref "JP4") (pin "3") (pinfunction "3_3") (pintype "passive"))
      (node (ref "JP4") (pin "4") (pinfunction "4_4") (pintype "passive"))
    )
    (net (code "65") (name "RB7{slash}PGD") (class "Default")
      (node (ref "JP4") (pin "1") (pinfunction "1_1") (pintype "passive"))
      (node (ref "JP4") (pin "2") (pinfunction "2_2") (pintype "passive"))
    )
    (net (code "66") (name "RC0") (class "Default")
      (node (ref "JP2") (pin "29") (pinfunction "29_29") (pintype "passive"))
      (node (ref "JP2") (pin "30") (pinfunction "30_30") (pintype "passive"))
    )
    (net (code "67") (name "RC1") (class "Default")
      (node (ref "JP2") (pin "31") (pinfunction "31_31") (pintype "passive"))
      (node (ref "JP2") (pin "32") (pinfunction "32_32") (pintype "passive"))
    )
    (net (code "68") (name "RC2") (class "Default")
      (node (ref "JP2") (pin "33") (pinfunction "33_33") (pintype "passive"))
      (node (ref "JP2") (pin "34") (pinfunction "34_34") (pintype "passive"))
    )
    (net (code "69") (name "RC3") (class "Default")
      (node (ref "JP2") (pin "35") (pinfunction "35_35") (pintype "passive"))
      (node (ref "JP2") (pin "36") (pinfunction "36_36") (pintype "passive"))
    )
    (net (code "70") (name "RC4") (class "Default")
      (node (ref "JP4") (pin "35") (pinfunction "35_35") (pintype "passive"))
      (node (ref "JP4") (pin "36") (pinfunction "36_36") (pintype "passive"))
    )
    (net (code "71") (name "RC5") (class "Default")
      (node (ref "JP4") (pin "33") (pinfunction "33_33") (pintype "passive"))
      (node (ref "JP4") (pin "34") (pinfunction "34_34") (pintype "passive"))
    )
    (net (code "72") (name "RC6") (class "Default")
      (node (ref "JP4") (pin "31") (pinfunction "31_31") (pintype "passive"))
      (node (ref "JP4") (pin "32") (pinfunction "32_32") (pintype "passive"))
    )
    (net (code "73") (name "RC7") (class "Default")
      (node (ref "JP4") (pin "29") (pinfunction "29_29") (pintype "passive"))
      (node (ref "JP4") (pin "30") (pinfunction "30_30") (pintype "passive"))
    )
    (net (code "74") (name "RED_ON") (class "Default")
      (node (ref "JP2") (pin "15") (pinfunction "15_15") (pintype "passive"))
      (node (ref "JP2") (pin "16") (pinfunction "16_16") (pintype "passive"))
      (node (ref "SJ18") (pin "2") (pinfunction "2_2") (pintype "passive"))
    )
    (net (code "75") (name "SWITCH1_OUT") (class "Default")
      (node (ref "JP2") (pin "37") (pinfunction "37_37") (pintype "passive"))
      (node (ref "JP2") (pin "38") (pinfunction "38_38") (pintype "passive"))
      (node (ref "SJ15") (pin "2") (pinfunction "2_2") (pintype "passive"))
    )
    (net (code "76") (name "SWITCH2_OUT") (class "Default")
      (node (ref "JP2") (pin "39") (pinfunction "39_39") (pintype "passive"))
      (node (ref "JP2") (pin "40") (pinfunction "40_40") (pintype "passive"))
      (node (ref "SJ14") (pin "2") (pinfunction "2_2") (pintype "passive"))
    )
    (net (code "77") (name "TEMP1_OUT") (class "Default")
      (node (ref "JP4") (pin "39") (pinfunction "39_39") (pintype "passive"))
      (node (ref "JP4") (pin "40") (pinfunction "40_40") (pintype "passive"))
      (node (ref "SJ4") (pin "2") (pinfunction "2_2") (pintype "passive"))
    )
    (net (code "78") (name "TEMP2_OUT") (class "Default")
      (node (ref "JP4") (pin "37") (pinfunction "37_37") (pintype "passive"))
      (node (ref "JP4") (pin "38") (pinfunction "38_38") (pintype "passive"))
      (node (ref "SJ3") (pin "2") (pinfunction "2_2") (pintype "passive"))
    )
    (net (code "79") (name "TRIM_OUT") (class "Default")
      (node (ref "JP4") (pin "23") (pinfunction "23_23") (pintype "passive"))
      (node (ref "JP4") (pin "24") (pinfunction "24_24") (pintype "passive"))
      (node (ref "SJ19") (pin "1") (pinfunction "1_1") (pintype "passive"))
    )
    (net (code "80") (name "VDD") (class "Default")
      (node (ref "C1") (pin "1") (pinfunction "1_1") (pintype "passive"))
      (node (ref "C2") (pin "1") (pinfunction "1_1") (pintype "passive"))
      (node (ref "JP1") (pin "2") (pinfunction "2_2") (pintype "passive"))
      (node (ref "JP2") (pin "21") (pinfunction "21_21") (pintype "passive"))
      (node (ref "JP2") (pin "22") (pinfunction "22_22") (pintype "passive"))
      (node (ref "JP4") (pin "17") (pinfunction "17_17") (pintype "passive"))
      (node (ref "JP4") (pin "18") (pinfunction "18_18") (pintype "passive"))
      (node (ref "JP5") (pin "2") (pinfunction "2_2") (pintype "passive"))
      (node (ref "LED9") (pin "A") (pinfunction "A_A") (pintype "passive"))
      (node (ref "R2") (pin "2") (pinfunction "2_2") (pintype "passive"))
      (node (ref "R3") (pin "2") (pinfunction "2_2") (pintype "passive"))
      (node (ref "S1") (pin "3") (pinfunction "2_3") (pintype "passive"))
      (node (ref "S2") (pin "3") (pinfunction "2_3") (pintype "passive"))
      (node (ref "SW1") (pin "10") (pinfunction "10_10") (pintype "bidirectional"))
      (node (ref "SW1") (pin "11") (pinfunction "11_11") (pintype "bidirectional"))
      (node (ref "SW1") (pin "12") (pinfunction "12_12") (pintype "bidirectional"))
      (node (ref "SW1") (pin "7") (pinfunction "7_7") (pintype "bidirectional"))
      (node (ref "SW1") (pin "8") (pinfunction "8_8") (pintype "bidirectional"))
      (node (ref "SW1") (pin "9") (pinfunction "9_9") (pintype "bidirectional"))
      (node (ref "TM1") (pin "1") (pinfunction "A_1") (pintype "passive"))
      (node (ref "U$1") (pin "8") (pinfunction "VCC_8") (pintype "bidirectional"))
      (node (ref "U$2") (pin "1") (pinfunction "VDD_1") (pintype "power_in"))
      (node (ref "U1") (pin "5") (pinfunction "SHUTDOWN*_5") (pintype "passive"))
      (node (ref "U1") (pin "8") (pinfunction "+VS_8") (pintype "power_in"))
      (node (ref "U2") (pin "5") (pinfunction "SHUTDOWN*_5") (pintype "passive"))
      (node (ref "U2") (pin "8") (pinfunction "+VS_8") (pintype "power_in"))
    )
    (net (code "81") (name "unconnected-(U$2-N.C.-Pad3)") (class "Default")
      (node (ref "U$2") (pin "3") (pinfunction "N.C._3") (pintype "passive"))
    )
    (net (code "82") (name "unconnected-(U1-NC-Pad7)") (class "Default")
      (node (ref "U1") (pin "7") (pinfunction "NC_7") (pintype "passive"))
    )
    (net (code "83") (name "unconnected-(U1-NC_2-Pad2)") (class "Default")
      (node (ref "U1") (pin "2") (pinfunction "NC_2_2") (pintype "passive"))
    )
    (net (code "84") (name "unconnected-(U1-NC_3-Pad3)") (class "Default")
      (node (ref "U1") (pin "3") (pinfunction "NC_3_3") (pintype "passive"))
    )
    (net (code "85") (name "unconnected-(U1-NC_4-Pad6)") (class "Default")
      (node (ref "U1") (pin "6") (pinfunction "NC_4_6") (pintype "passive"))
    )
    (net (code "86") (name "unconnected-(U2-NC-Pad7)") (class "Default")
      (node (ref "U2") (pin "7") (pinfunction "NC_7") (pintype "passive"))
    )
    (net (code "87") (name "unconnected-(U2-NC_2-Pad2)") (class "Default")
      (node (ref "U2") (pin "2") (pinfunction "NC_2_2") (pintype "passive"))
    )
    (net (code "88") (name "unconnected-(U2-NC_3-Pad3)") (class "Default")
      (node (ref "U2") (pin "3") (pinfunction "NC_3_3") (pintype "passive"))
    )
    (net (code "89") (name "unconnected-(U2-NC_4-Pad6)") (class "Default")
      (node (ref "U2") (pin "6") (pinfunction "NC_4_6") (pintype "passive"))
    )
  )
)
